# Directional_Coupler.net
KiCad netlist of a schematic drawn in Altium Designer
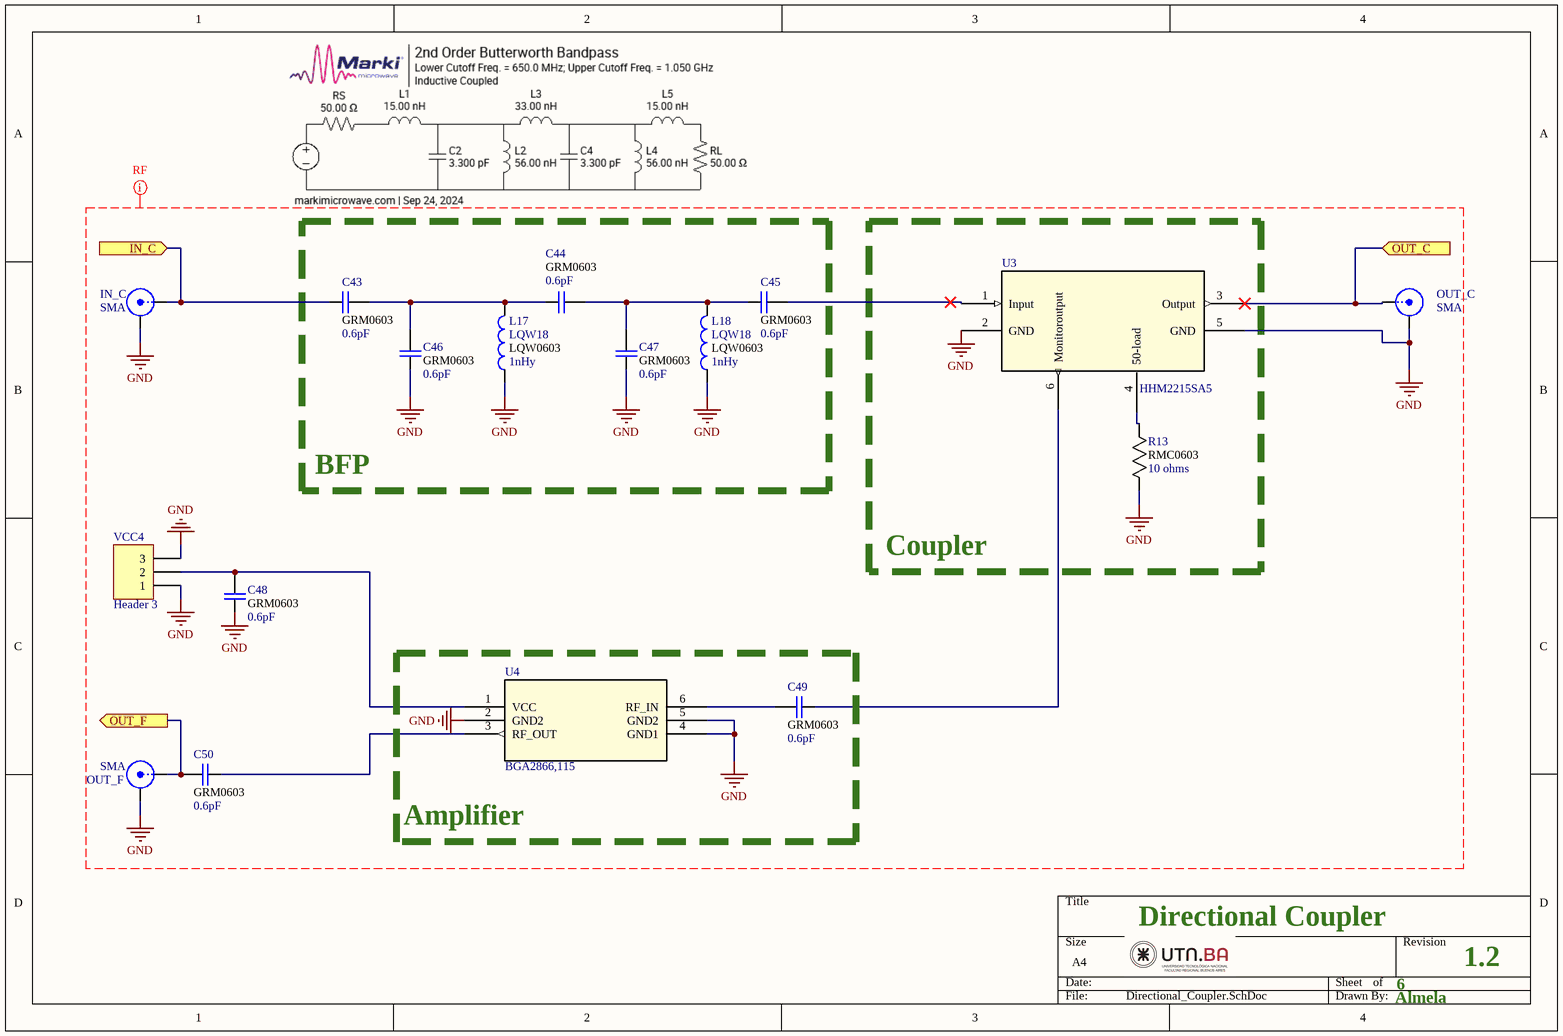
[diagram p0: Directional_Coupler.SchDoc]

(export (version "E")
  (design (tool "Eeschema 10.0.6"))
  (components
    (comp (ref "C43")
      (value "0.6pF")
      (footprint "GRM0603")
      (description "Capacitor GRM18 0603")
      (fields (field (name "Comment") "Cap 0603") (field (name "PUBLISHER") "Altium Limited"))
      (libsource (lib "Radar_RF_EAIII") (part "Cap"))
    )
    (comp (ref "C44")
      (value "0.6pF")
      (footprint "GRM0603")
      (description "Capacitor GRM18 0603")
      (fields (field (name "Comment") "Cap 0603") (field (name "PUBLISHER") "Altium Limited"))
      (libsource (lib "Radar_RF_EAIII") (part "Cap"))
    )
    (comp (ref "C45")
      (value "0.6pF")
      (footprint "GRM0603")
      (description "Capacitor GRM18 0603")
      (fields (field (name "Comment") "Cap 0603") (field (name "PUBLISHER") "Altium Limited"))
      (libsource (lib "Radar_RF_EAIII") (part "Cap"))
    )
    (comp (ref "C46")
      (value "0.6pF")
      (footprint "GRM0603")
      (description "Capacitor GRM18 0603")
      (fields (field (name "Comment") "Cap 0603") (field (name "PUBLISHER") "Altium Limited"))
      (libsource (lib "Radar_RF_EAIII") (part "Cap"))
    )
    (comp (ref "C47")
      (value "0.6pF")
      (footprint "GRM0603")
      (description "Capacitor GRM18 0603")
      (fields (field (name "Comment") "Cap 0603") (field (name "PUBLISHER") "Altium Limited"))
      (libsource (lib "Radar_RF_EAIII") (part "Cap"))
    )
    (comp (ref "C48")
      (value "0.6pF")
      (footprint "GRM0603")
      (description "Capacitor GRM18 0603")
      (fields (field (name "Comment") "Cap 0603") (field (name "PUBLISHER") "Altium Limited"))
      (libsource (lib "Radar_RF_EAIII") (part "Cap"))
    )
    (comp (ref "C49")
      (value "0.6pF")
      (footprint "GRM0603")
      (description "Capacitor GRM18 0603")
      (fields (field (name "Comment") "Cap 0603") (field (name "PUBLISHER") "Altium Limited"))
      (libsource (lib "Radar_RF_EAIII") (part "Cap"))
    )
    (comp (ref "C50")
      (value "0.6pF")
      (footprint "GRM0603")
      (description "Capacitor GRM18 0603")
      (fields (field (name "Comment") "Cap 0603") (field (name "PUBLISHER") "Altium Limited"))
      (libsource (lib "Radar_RF_EAIII") (part "Cap"))
    )
    (comp (ref "IN_C")
      (value "SMA")
      (footprint "SMA-142-0701-851_V2")
      (description "SMA Straight Connector")
      (fields (field (name "PUBLISHER") "Altium Limited"))
      (libsource (lib "Radar_RF_EAIII") (part "SMA"))
    )
    (comp (ref "L17")
      (value "LQW18")
      (footprint "INDC1608X100N")
      (description "Ind RF Chip Wirewound 18nH 5% 100MHz 40Q-Factor 550mA 0603 Paper T/R")
      (fields
        (field (name "MP") "LQW18AN18NJ00D")
        (field (name "PARAMETER 1") "LQW0603")
        (field (name "ALTIUM_VALUE") "1nHy")
      )
      (libsource (lib "Radar_RF_EAIII") (part "LQW18"))
    )
    (comp (ref "L18")
      (value "LQW18")
      (footprint "INDC1608X100N")
      (description "Ind RF Chip Wirewound 18nH 5% 100MHz 40Q-Factor 550mA 0603 Paper T/R")
      (fields
        (field (name "MP") "LQW18AN18NJ00D")
        (field (name "PARAMETER 1") "LQW0603")
        (field (name "ALTIUM_VALUE") "1nHy")
      )
      (libsource (lib "Radar_RF_EAIII") (part "LQW18"))
    )
    (comp (ref "OUT_C")
      (value "SMA")
      (footprint "SMA-142-0701-851_V2")
      (description "SMA Straight Connector")
      (fields (field (name "PUBLISHER") "Altium Limited"))
      (libsource (lib "Radar_RF_EAIII") (part "SMA"))
    )
    (comp (ref "OUT_F")
      (value "SMA")
      (footprint "SMA-142-0701-851")
      (description "SMB Straight Connector")
      (fields (field (name "PUBLISHER") "Altium Limited"))
      (libsource (lib "PCB_Project") (part "SMB"))
    )
    (comp (ref "R13")
      (value "10 ohms")
      (footprint "RMC0603")
      (description "Resistor RMC0603")
      (fields (field (name "Comment") "Resistor"))
      (libsource (lib "Radar_RF_EAIII") (part "Resistor"))
    )
    (comp (ref "U3")
      (value "HHM2215SA5")
      (footprint "HHM-6_1P6X0P8")
      (description "No Description Available")
      (libsource (lib "Radar_RF_EAIII") (part "HHM2215SA5"))
    )
    (comp (ref "U4")
      (value "BGA2866,115")
      (footprint "SOT363_NXP")
      (description "No Description Available")
      (libsource (lib "Radar_RF_EAIII") (part "BGA2866,115"))
    )
    (comp (ref "VCC4")
      (value "Header 3")
      (footprint "HDR1X3")
      (description "Header, 3-Pin")
      (fields (field (name "PUBLISHER") "Altium Limited"))
      (libsource (lib "Miscellaneous Connectors") (part "Header 3"))
    )
  )
  (nets
    (net (code "1") (name "/IN_C") (class "Default")
      (node (ref "C43") (pin "1") (pinfunction "1_1") (pintype "passive"))
      (node (ref "IN_C") (pin "1") (pinfunction "X_1") (pintype "passive"))
    )
    (net (code "2") (name "/OUT_C") (class "Default")
      (node (ref "OUT_C") (pin "1") (pinfunction "X_1") (pintype "passive"))
      (node (ref "U3") (pin "3") (pinfunction "Output_3") (pintype "output"))
    )
    (net (code "3") (name "/OUT_F") (class "Default")
      (node (ref "C50") (pin "2") (pinfunction "2_2") (pintype "passive"))
      (node (ref "OUT_F") (pin "1") (pinfunction "X_1") (pintype "passive"))
    )
    (net (code "4") (name "GND") (class "Default")
      (node (ref "C46") (pin "1") (pinfunction "1_1") (pintype "passive"))
      (node (ref "C47") (pin "1") (pinfunction "1_1") (pintype "passive"))
      (node (ref "C48") (pin "1") (pinfunction "1_1") (pintype "passive"))
      (node (ref "IN_C") (pin "2") (pinfunction "Y_2") (pintype "passive"))
      (node (ref "L17") (pin "1") (pinfunction "1_1") (pintype "passive"))
      (node (ref "L18") (pin "1") (pinfunction "1_1") (pintype "passive"))
      (node (ref "OUT_C") (pin "2") (pinfunction "Y_2") (pintype "passive"))
      (node (ref "OUT_F") (pin "2") (pinfunction "Y_2") (pintype "passive"))
      (node (ref "R13") (pin "1") (pinfunction "1_1") (pintype "passive"))
      (node (ref "U3") (pin "2") (pinfunction "GND_2") (pintype "power_in"))
      (node (ref "U3") (pin "5") (pinfunction "GND_5") (pintype "power_in"))
      (node (ref "U4") (pin "2") (pinfunction "GND2_2") (pintype "power_in"))
      (node (ref "U4") (pin "4") (pinfunction "GND1_4") (pintype "power_in"))
      (node (ref "U4") (pin "5") (pinfunction "GND2_5") (pintype "power_in"))
      (node (ref "VCC4") (pin "1") (pinfunction "1_1") (pintype "passive"))
      (node (ref "VCC4") (pin "3") (pinfunction "3_3") (pintype "passive"))
    )
    (net (code "5") (name "Net-(C43-Pad2)") (class "Default")
      (node (ref "C43") (pin "2") (pinfunction "2_2") (pintype "passive"))
      (node (ref "C44") (pin "1") (pinfunction "1_1") (pintype "passive"))
      (node (ref "C46") (pin "2") (pinfunction "2_2") (pintype "passive"))
      (node (ref "L17") (pin "2") (pinfunction "2_2") (pintype "passive"))
    )
    (net (code "6") (name "Net-(C44-Pad2)") (class "Default")
      (node (ref "C44") (pin "2") (pinfunction "2_2") (pintype "passive"))
      (node (ref "C45") (pin "1") (pinfunction "1_1") (pintype "passive"))
      (node (ref "C47") (pin "2") (pinfunction "2_2") (pintype "passive"))
      (node (ref "L18") (pin "2") (pinfunction "2_2") (pintype "passive"))
    )
    (net (code "7") (name "Net-(U3-50-load)") (class "Default")
      (node (ref "R13") (pin "2") (pinfunction "2_2") (pintype "passive"))
      (node (ref "U3") (pin "4") (pinfunction "50-load_4") (pintype "passive"))
    )
    (net (code "8") (name "Net-(U3-Input)") (class "Default")
      (node (ref "C45") (pin "2") (pinfunction "2_2") (pintype "passive"))
      (node (ref "U3") (pin "1") (pinfunction "Input_1") (pintype "input"))
    )
    (net (code "9") (name "Net-(U3-Monitoroutput)") (class "Default")
      (node (ref "C49") (pin "1") (pinfunction "1_1") (pintype "passive"))
      (node (ref "U3") (pin "6") (pinfunction "Monitoroutput_6") (pintype "output"))
    )
    (net (code "10") (name "Net-(U4-RF_IN)") (class "Default")
      (node (ref "C49") (pin "2") (pinfunction "2_2") (pintype "passive"))
      (node (ref "U4") (pin "6") (pinfunction "RF_IN_6") (pintype "passive"))
    )
    (net (code "11") (name "Net-(U4-RF_OUT)") (class "Default")
      (node (ref "C50") (pin "1") (pinfunction "1_1") (pintype "passive"))
      (node (ref "U4") (pin "3") (pinfunction "RF_OUT_3") (pintype "output"))
    )
    (net (code "12") (name "Net-(U4-VCC)") (class "Default")
      (node (ref "C48") (pin "2") (pinfunction "2_2") (pintype "passive"))
      (node (ref "U4") (pin "1") (pinfunction "VCC_1") (pintype "power_in"))
      (node (ref "VCC4") (pin "2") (pinfunction "2_2") (pintype "passive"))
    )
  )
)
